# NINJA-001.net
KiCad netlist of a schematic drawn in EAGLE
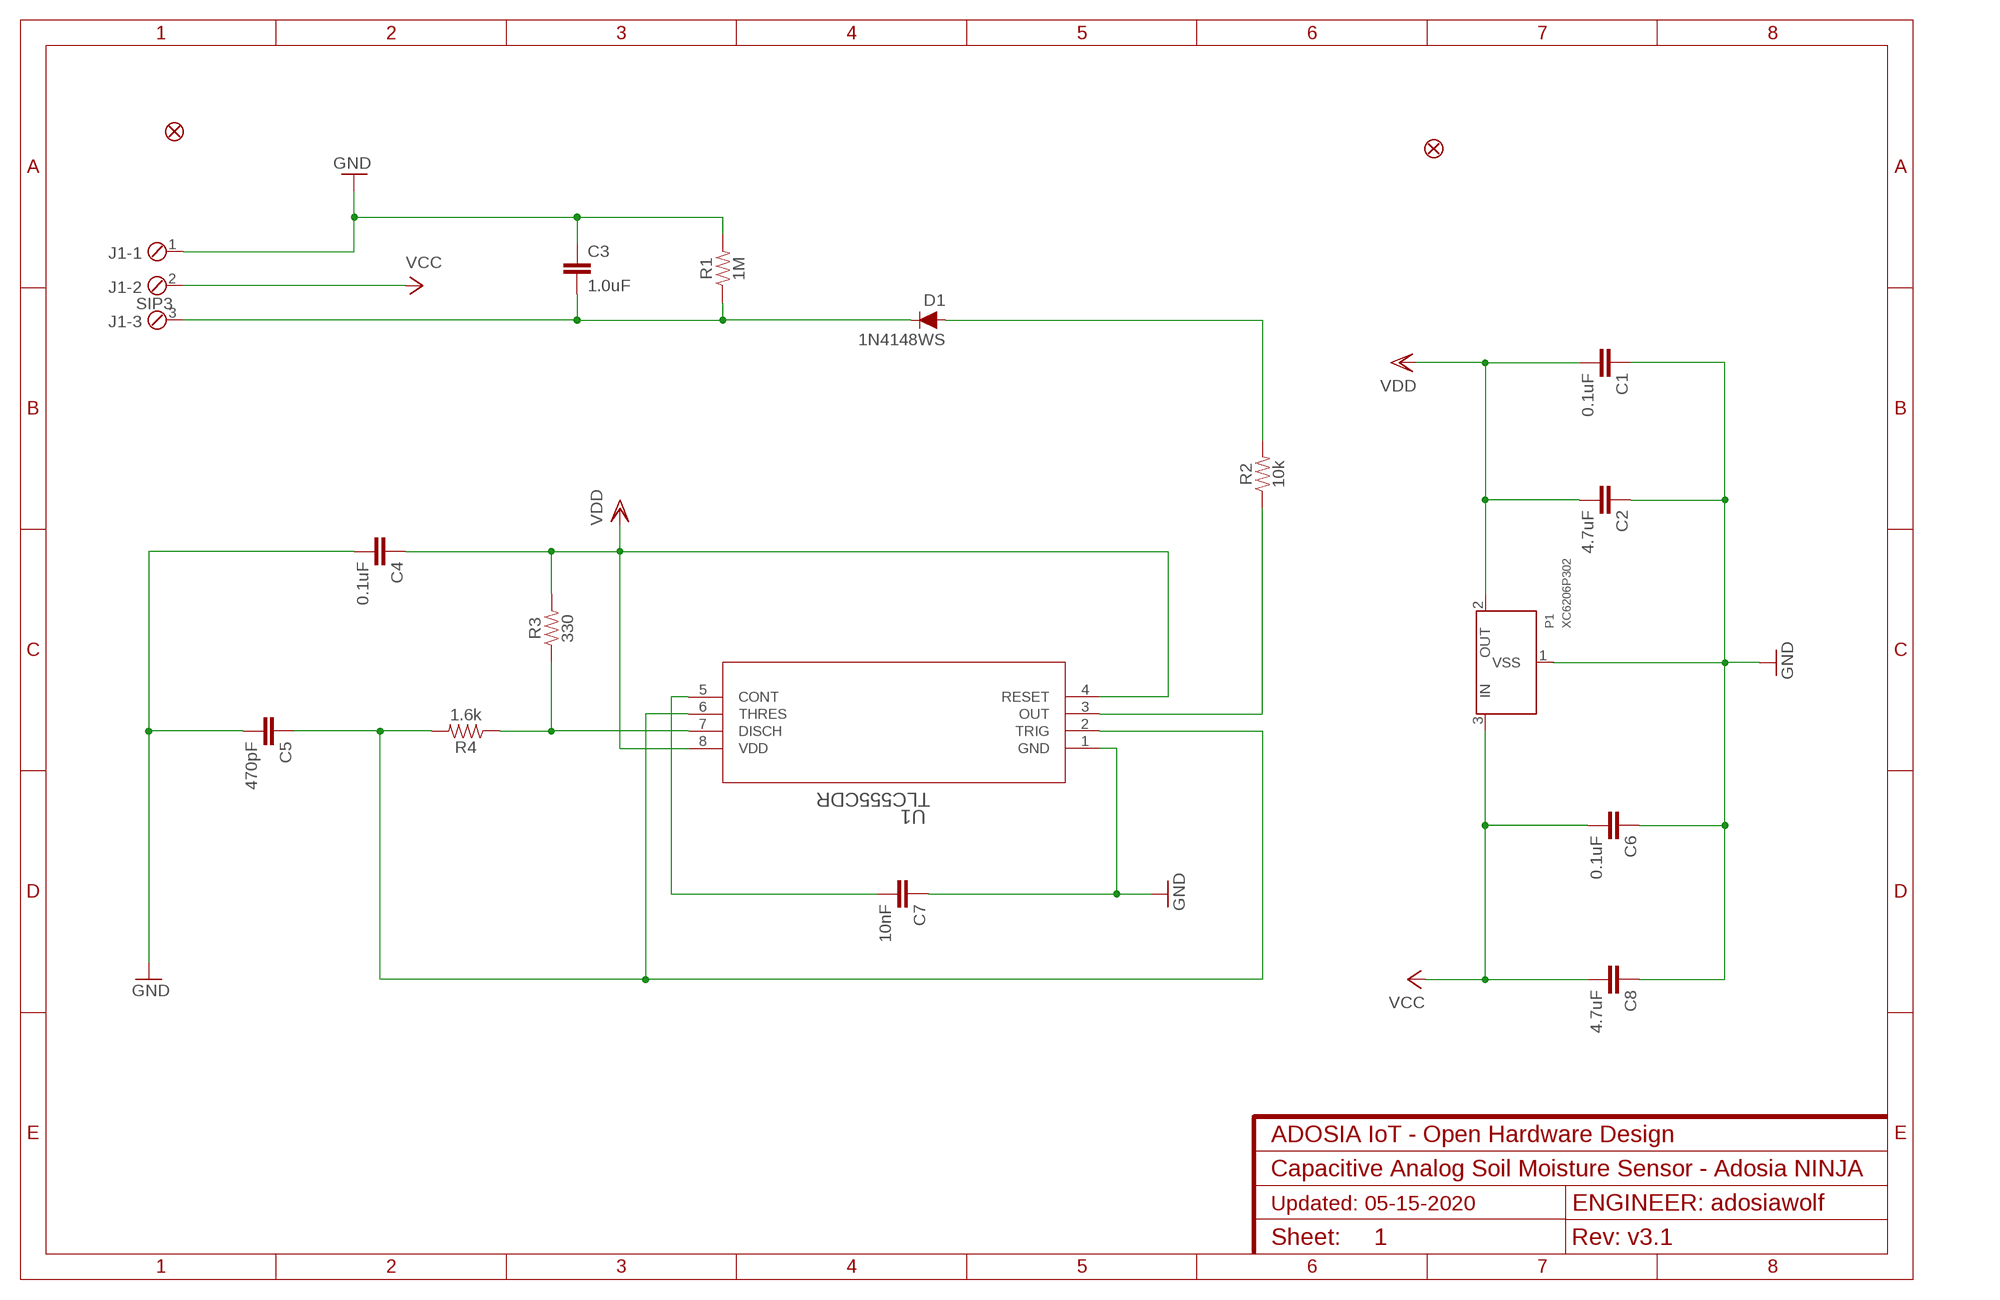
[diagram p0: schematic, sheet 1]

(export (version "E")
  (design (tool "Eeschema 10.0.6"))
  (components
    (comp (ref "C1")
      (value "0.1uF")
      (footprint "eagle-import:0603")
      (libsource (lib "eagle-import") (part "0.1UF-0603-25V-5%"))
    )
    (comp (ref "C2")
      (value "4.7uF")
      (footprint "eagle-import:0603")
      (libsource (lib "eagle-import") (part "4.7UF0603"))
    )
    (comp (ref "C3")
      (value "1.0uF")
      (footprint "eagle-import:0603")
      (libsource (lib "eagle-import") (part "1.0UF-0603-16V-10%"))
    )
    (comp (ref "C4")
      (value "0.1uF")
      (footprint "eagle-import:0603")
      (libsource (lib "eagle-import") (part "0.1UF-0603-25V-5%"))
    )
    (comp (ref "C5")
      (value "470pF")
      (footprint "eagle-import:0603")
      (libsource (lib "eagle-import") (part "470PF-0603-50V-5%"))
    )
    (comp (ref "C6")
      (value "0.1uF")
      (footprint "eagle-import:0603")
      (libsource (lib "eagle-import") (part "0.1UF-0603-25V-5%"))
    )
    (comp (ref "C7")
      (value "10nF")
      (footprint "eagle-import:0603")
      (libsource (lib "eagle-import") (part "10NF-0603-50V-10%"))
    )
    (comp (ref "C8")
      (value "4.7uF")
      (footprint "eagle-import:0603")
      (libsource (lib "eagle-import") (part "4.7UF0603"))
    )
    (comp (ref "D1")
      (value "1N4148WS")
      (footprint "eagle-import:SOD-323")
      (libsource (lib "eagle-import") (part "DIODE-BAS16J"))
    )
    (comp (ref "FD1")
      (value "FIDUCIAL1X2")
      (footprint "eagle-import:FIDUCIAL-1X2")
      (libsource (lib "eagle-import") (part "FIDUCIAL1X2"))
    )
    (comp (ref "FD2")
      (value "FIDUCIAL1X2")
      (footprint "eagle-import:FIDUCIAL-1X2")
      (libsource (lib "eagle-import") (part "FIDUCIAL1X2"))
    )
    (comp (ref "J1")
      (value "SIP3")
      (footprint "eagle-import:3POL254")
      (libsource (lib "eagle-import") (part "MPT3"))
    )
    (comp (ref "P1")
      (value "XC6206P302")
      (footprint "eagle-import:XC6206_SOT-23")
      (libsource (lib "eagle-import") (part "XC6206SOT-23"))
    )
    (comp (ref "R1")
      (value "1M")
      (footprint "eagle-import:0603")
      (libsource (lib "eagle-import") (part "1MOHM-0603-1/4W-5%"))
    )
    (comp (ref "R2")
      (value "10k")
      (footprint "eagle-import:0603")
      (libsource (lib "eagle-import") (part "10KOHM-0603-1/10W-1%"))
    )
    (comp (ref "R3")
      (value "330")
      (footprint "eagle-import:0603")
      (libsource (lib "eagle-import") (part "330OHM-0603-1/10W-1%"))
    )
    (comp (ref "R4")
      (value "1.6k")
      (footprint "eagle-import:0603")
      (libsource (lib "eagle-import") (part "1.6KOHM-0603-1/10W-1%"))
    )
    (comp (ref "U1")
      (value "TLC555CDR")
      (footprint "eagle-import:D8")
      (libsource (lib "eagle-import") (part "TLC555CDR"))
    )
  )
  (nets
    (net (code "1") (name "GND") (class "Default")
      (node (ref "C1") (pin "1") (pinfunction "1_1") (pintype "passive"))
      (node (ref "C2") (pin "1") (pinfunction "1_1") (pintype "passive"))
      (node (ref "C3") (pin "1") (pinfunction "1_1") (pintype "passive"))
      (node (ref "C4") (pin "2") (pinfunction "2_2") (pintype "passive"))
      (node (ref "C5") (pin "2") (pinfunction "2_2") (pintype "passive"))
      (node (ref "C6") (pin "1") (pinfunction "1_1") (pintype "passive"))
      (node (ref "C7") (pin "1") (pinfunction "1_1") (pintype "passive"))
      (node (ref "C8") (pin "1") (pinfunction "1_1") (pintype "passive"))
      (node (ref "J1") (pin "1") (pinfunction "1_1") (pintype "passive"))
      (node (ref "P1") (pin "1") (pinfunction "VSS_1") (pintype "bidirectional"))
      (node (ref "R1") (pin "2") (pinfunction "2_2") (pintype "passive"))
      (node (ref "U1") (pin "1") (pinfunction "GND_1") (pintype "power_in"))
    )
    (net (code "2") (name "Net-(D1-PadA)") (class "Default")
      (node (ref "D1") (pin "A") (pinfunction "A_A") (pintype "passive"))
      (node (ref "R2") (pin "2") (pinfunction "2_2") (pintype "passive"))
    )
    (net (code "3") (name "Net-(J1C-1)") (class "Default")
      (node (ref "C3") (pin "2") (pinfunction "2_2") (pintype "passive"))
      (node (ref "D1") (pin "C") (pinfunction "C_C") (pintype "passive"))
      (node (ref "J1") (pin "3") (pinfunction "1_3") (pintype "passive"))
      (node (ref "R1") (pin "1") (pinfunction "1_1") (pintype "passive"))
    )
    (net (code "4") (name "Net-(U1-CONT)") (class "Default")
      (node (ref "C7") (pin "2") (pinfunction "2_2") (pintype "passive"))
      (node (ref "U1") (pin "5") (pinfunction "CONT_5") (pintype "input"))
    )
    (net (code "5") (name "Net-(U1-DISCH)") (class "Default")
      (node (ref "R3") (pin "1") (pinfunction "1_1") (pintype "passive"))
      (node (ref "R4") (pin "1") (pinfunction "1_1") (pintype "passive"))
      (node (ref "U1") (pin "7") (pinfunction "DISCH_7") (pintype "output"))
    )
    (net (code "6") (name "Net-(U1-OUT)") (class "Default")
      (node (ref "R2") (pin "1") (pinfunction "1_1") (pintype "passive"))
      (node (ref "U1") (pin "3") (pinfunction "OUT_3") (pintype "output"))
    )
    (net (code "7") (name "Net-(U1-THRES)") (class "Default")
      (node (ref "C5") (pin "1") (pinfunction "1_1") (pintype "passive"))
      (node (ref "R4") (pin "2") (pinfunction "2_2") (pintype "passive"))
      (node (ref "U1") (pin "2") (pinfunction "TRIG_2") (pintype "input"))
      (node (ref "U1") (pin "6") (pinfunction "THRES_6") (pintype "input"))
    )
    (net (code "8") (name "VCC") (class "Default")
      (node (ref "C6") (pin "2") (pinfunction "2_2") (pintype "passive"))
      (node (ref "C8") (pin "2") (pinfunction "2_2") (pintype "passive"))
      (node (ref "J1") (pin "2") (pinfunction "1_2") (pintype "passive"))
      (node (ref "P1") (pin "3") (pinfunction "IN_3") (pintype "bidirectional"))
    )
    (net (code "9") (name "VDD") (class "Default")
      (node (ref "C1") (pin "2") (pinfunction "2_2") (pintype "passive"))
      (node (ref "C2") (pin "2") (pinfunction "2_2") (pintype "passive"))
      (node (ref "C4") (pin "1") (pinfunction "1_1") (pintype "passive"))
      (node (ref "P1") (pin "2") (pinfunction "OUT_2") (pintype "bidirectional"))
      (node (ref "R3") (pin "2") (pinfunction "2_2") (pintype "passive"))
      (node (ref "U1") (pin "4") (pinfunction "RESET_4") (pintype "input"))
      (node (ref "U1") (pin "8") (pinfunction "VDD_8") (pintype "power_in"))
    )
  )
)
